# design.net
KiCad netlist of a schematic drawn in Altium Designer
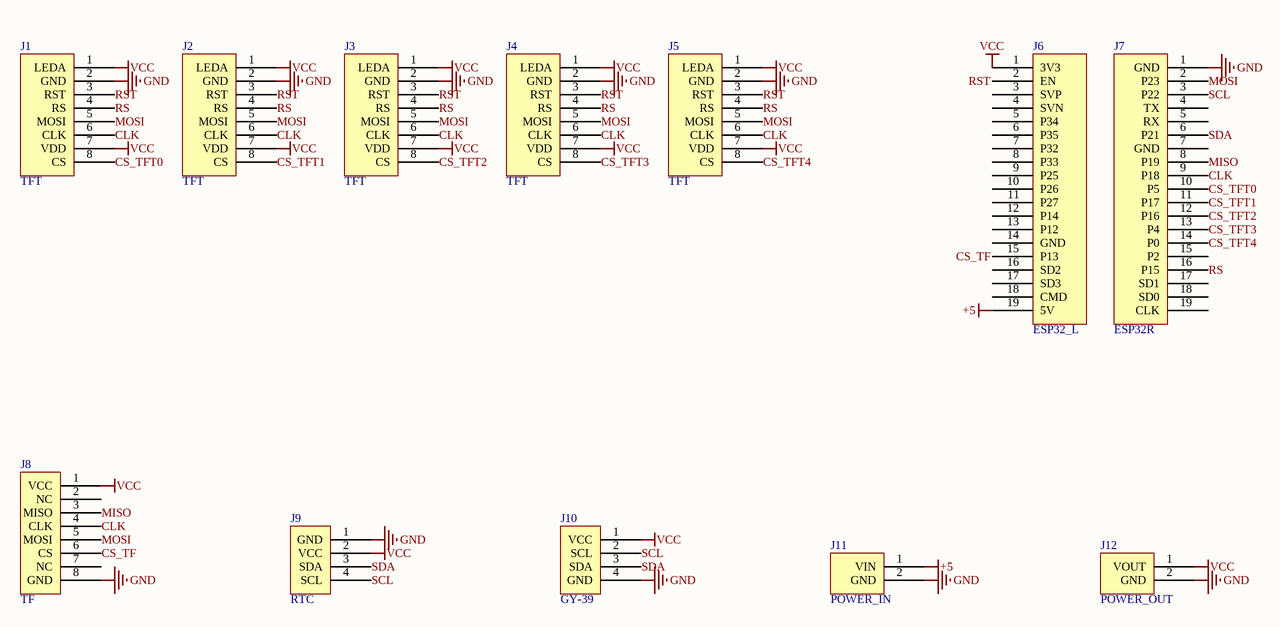
[diagram p0: 原理图.SchDoc]

(export (version "E")
  (design (tool "Eeschema 10.0.6"))
  (components
    (comp (ref "J1")
      (value "TFT")
      (footprint "MHDR1X8")
      (description "TFT槽")
      (libsource (lib "*") (part "1.14 tft"))
    )
    (comp (ref "J2")
      (value "TFT")
      (footprint "MHDR1X8")
      (description "TFT槽")
      (libsource (lib "*") (part "1.14 tft"))
    )
    (comp (ref "J3")
      (value "TFT")
      (footprint "MHDR1X8")
      (description "TFT槽")
      (libsource (lib "*") (part "1.14 tft"))
    )
    (comp (ref "J4")
      (value "TFT")
      (footprint "MHDR1X8")
      (description "TFT槽")
      (libsource (lib "*") (part "1.14 tft"))
    )
    (comp (ref "J5")
      (value "TFT")
      (footprint "MHDR1X8")
      (description "TFT槽")
      (libsource (lib "*") (part "1.14 tft"))
    )
    (comp (ref "J6")
      (value "ESP32_L")
      (footprint "MHDR1X19")
      (description "ESP32左槽")
      (libsource (lib "*") (part "ESP32-S_L"))
    )
    (comp (ref "J7")
      (value "ESP32R")
      (footprint "MHDR1X19")
      (description "ESP32右槽")
      (libsource (lib "*") (part "ESP32-S_R"))
    )
    (comp (ref "J8")
      (value "TF")
      (footprint "MHDR1X8")
      (description "TF卡模块槽")
      (libsource (lib "*") (part "TF card"))
    )
    (comp (ref "J9")
      (value "RTC")
      (footprint "MHDR1X4")
      (description "时钟模块槽")
      (libsource (lib "*") (part "RTC"))
    )
    (comp (ref "J10")
      (value "GY-39")
      (footprint "MHDR1X4")
      (description "GY-39模块槽")
      (libsource (lib "*") (part "GY-39"))
    )
    (comp (ref "J11") (value "POWER_IN") (footprint "MHDR1X2") (libsource (lib "*") (part "POWER_IN")))
    (comp (ref "J12") (value "POWER_OUT") (footprint "MHDR1X2") (libsource (lib "*") (part "POWER_OUT")))
  )
  (nets
    (net (code "1") (name "+5") (class "Default")
      (node (ref "J11") (pin "1") (pinfunction "VIN_1") (pintype "passive"))
      (node (ref "J6") (pin "19") (pinfunction "5V_19") (pintype "passive"))
    )
    (net (code "2") (name "/CLK") (class "Default")
      (node (ref "J1") (pin "6") (pinfunction "CLK_6") (pintype "passive"))
      (node (ref "J2") (pin "6") (pinfunction "CLK_6") (pintype "passive"))
      (node (ref "J3") (pin "6") (pinfunction "CLK_6") (pintype "passive"))
      (node (ref "J4") (pin "6") (pinfunction "CLK_6") (pintype "passive"))
      (node (ref "J5") (pin "6") (pinfunction "CLK_6") (pintype "passive"))
      (node (ref "J7") (pin "9") (pinfunction "P18_9") (pintype "passive"))
      (node (ref "J8") (pin "4") (pinfunction "CLK_4") (pintype "passive"))
    )
    (net (code "3") (name "/CS_TF") (class "Default")
      (node (ref "J6") (pin "15") (pinfunction "P13_15") (pintype "passive"))
      (node (ref "J8") (pin "6") (pinfunction "CS_6") (pintype "passive"))
    )
    (net (code "4") (name "/CS_TFT0") (class "Default")
      (node (ref "J1") (pin "8") (pinfunction "CS_8") (pintype "passive"))
      (node (ref "J7") (pin "10") (pinfunction "P5_10") (pintype "passive"))
    )
    (net (code "5") (name "/CS_TFT1") (class "Default")
      (node (ref "J2") (pin "8") (pinfunction "CS_8") (pintype "passive"))
      (node (ref "J7") (pin "11") (pinfunction "P17_11") (pintype "passive"))
    )
    (net (code "6") (name "/CS_TFT2") (class "Default")
      (node (ref "J3") (pin "8") (pinfunction "CS_8") (pintype "passive"))
      (node (ref "J7") (pin "12") (pinfunction "P16_12") (pintype "passive"))
    )
    (net (code "7") (name "/CS_TFT3") (class "Default")
      (node (ref "J4") (pin "8") (pinfunction "CS_8") (pintype "passive"))
      (node (ref "J7") (pin "13") (pinfunction "P4_13") (pintype "passive"))
    )
    (net (code "8") (name "/CS_TFT4") (class "Default")
      (node (ref "J5") (pin "8") (pinfunction "CS_8") (pintype "passive"))
      (node (ref "J7") (pin "14") (pinfunction "P0_14") (pintype "passive"))
    )
    (net (code "9") (name "/MISO") (class "Default")
      (node (ref "J7") (pin "8") (pinfunction "P19_8") (pintype "passive"))
      (node (ref "J8") (pin "3") (pinfunction "MISO_3") (pintype "passive"))
    )
    (net (code "10") (name "/MOSI") (class "Default")
      (node (ref "J1") (pin "5") (pinfunction "MOSI_5") (pintype "passive"))
      (node (ref "J2") (pin "5") (pinfunction "MOSI_5") (pintype "passive"))
      (node (ref "J3") (pin "5") (pinfunction "MOSI_5") (pintype "passive"))
      (node (ref "J4") (pin "5") (pinfunction "MOSI_5") (pintype "passive"))
      (node (ref "J5") (pin "5") (pinfunction "MOSI_5") (pintype "passive"))
      (node (ref "J7") (pin "2") (pinfunction "P23_2") (pintype "passive"))
      (node (ref "J8") (pin "5") (pinfunction "MOSI_5") (pintype "passive"))
    )
    (net (code "11") (name "/RS") (class "Default")
      (node (ref "J1") (pin "4") (pinfunction "RS_4") (pintype "passive"))
      (node (ref "J2") (pin "4") (pinfunction "RS_4") (pintype "passive"))
      (node (ref "J3") (pin "4") (pinfunction "RS_4") (pintype "passive"))
      (node (ref "J4") (pin "4") (pinfunction "RS_4") (pintype "passive"))
      (node (ref "J5") (pin "4") (pinfunction "RS_4") (pintype "passive"))
      (node (ref "J7") (pin "16") (pinfunction "P15_16") (pintype "passive"))
    )
    (net (code "12") (name "/RST") (class "Default")
      (node (ref "J1") (pin "3") (pinfunction "RST_3") (pintype "passive"))
      (node (ref "J2") (pin "3") (pinfunction "RST_3") (pintype "passive"))
      (node (ref "J3") (pin "3") (pinfunction "RST_3") (pintype "passive"))
      (node (ref "J4") (pin "3") (pinfunction "RST_3") (pintype "passive"))
      (node (ref "J5") (pin "3") (pinfunction "RST_3") (pintype "passive"))
      (node (ref "J6") (pin "2") (pinfunction "EN_2") (pintype "passive"))
    )
    (net (code "13") (name "/SCL") (class "Default")
      (node (ref "J10") (pin "2") (pinfunction "SCL_2") (pintype "passive"))
      (node (ref "J7") (pin "3") (pinfunction "P22_3") (pintype "passive"))
      (node (ref "J9") (pin "4") (pinfunction "SCL_4") (pintype "passive"))
    )
    (net (code "14") (name "/SDA") (class "Default")
      (node (ref "J10") (pin "3") (pinfunction "SDA_3") (pintype "passive"))
      (node (ref "J7") (pin "6") (pinfunction "P21_6") (pintype "passive"))
      (node (ref "J9") (pin "3") (pinfunction "SDA_3") (pintype "passive"))
    )
    (net (code "15") (name "GND") (class "Default")
      (node (ref "J1") (pin "2") (pinfunction "GND_2") (pintype "passive"))
      (node (ref "J10") (pin "4") (pinfunction "GND_4") (pintype "passive"))
      (node (ref "J11") (pin "2") (pinfunction "GND_2") (pintype "passive"))
      (node (ref "J12") (pin "2") (pinfunction "GND_2") (pintype "passive"))
      (node (ref "J2") (pin "2") (pinfunction "GND_2") (pintype "passive"))
      (node (ref "J3") (pin "2") (pinfunction "GND_2") (pintype "passive"))
      (node (ref "J4") (pin "2") (pinfunction "GND_2") (pintype "passive"))
      (node (ref "J5") (pin "2") (pinfunction "GND_2") (pintype "passive"))
      (node (ref "J7") (pin "1") (pinfunction "GND_1") (pintype "passive"))
      (node (ref "J8") (pin "8") (pinfunction "GND_8") (pintype "passive"))
      (node (ref "J9") (pin "1") (pinfunction "GND_1") (pintype "passive"))
    )
    (net (code "16") (name "VCC") (class "Default")
      (node (ref "J1") (pin "1") (pinfunction "LEDA_1") (pintype "passive"))
      (node (ref "J1") (pin "7") (pinfunction "VDD_7") (pintype "passive"))
      (node (ref "J10") (pin "1") (pinfunction "VCC_1") (pintype "passive"))
      (node (ref "J12") (pin "1") (pinfunction "VOUT_1") (pintype "passive"))
      (node (ref "J2") (pin "1") (pinfunction "LEDA_1") (pintype "passive"))
      (node (ref "J2") (pin "7") (pinfunction "VDD_7") (pintype "passive"))
      (node (ref "J3") (pin "1") (pinfunction "LEDA_1") (pintype "passive"))
      (node (ref "J3") (pin "7") (pinfunction "VDD_7") (pintype "passive"))
      (node (ref "J4") (pin "1") (pinfunction "LEDA_1") (pintype "passive"))
      (node (ref "J4") (pin "7") (pinfunction "VDD_7") (pintype "passive"))
      (node (ref "J5") (pin "1") (pinfunction "LEDA_1") (pintype "passive"))
      (node (ref "J5") (pin "7") (pinfunction "VDD_7") (pintype "passive"))
      (node (ref "J6") (pin "1") (pinfunction "3V3_1") (pintype "passive"))
      (node (ref "J8") (pin "1") (pinfunction "VCC_1") (pintype "passive"))
      (node (ref "J9") (pin "2") (pinfunction "VCC_2") (pintype "passive"))
    )
    (net (code "17") (name "unconnected-(J6-CMD-Pad18)") (class "Default")
      (node (ref "J6") (pin "18") (pinfunction "CMD_18") (pintype "passive"))
    )
    (net (code "18") (name "unconnected-(J6-GND-Pad14)") (class "Default")
      (node (ref "J6") (pin "14") (pinfunction "GND_14") (pintype "passive"))
    )
    (net (code "19") (name "unconnected-(J6-P12-Pad13)") (class "Default")
      (node (ref "J6") (pin "13") (pinfunction "P12_13") (pintype "passive"))
    )
    (net (code "20") (name "unconnected-(J6-P14-Pad12)") (class "Default")
      (node (ref "J6") (pin "12") (pinfunction "P14_12") (pintype "passive"))
    )
    (net (code "21") (name "unconnected-(J6-P25-Pad9)") (class "Default")
      (node (ref "J6") (pin "9") (pinfunction "P25_9") (pintype "passive"))
    )
    (net (code "22") (name "unconnected-(J6-P26-Pad10)") (class "Default")
      (node (ref "J6") (pin "10") (pinfunction "P26_10") (pintype "passive"))
    )
    (net (code "23") (name "unconnected-(J6-P27-Pad11)") (class "Default")
      (node (ref "J6") (pin "11") (pinfunction "P27_11") (pintype "passive"))
    )
    (net (code "24") (name "unconnected-(J6-P32-Pad7)") (class "Default")
      (node (ref "J6") (pin "7") (pinfunction "P32_7") (pintype "passive"))
    )
    (net (code "25") (name "unconnected-(J6-P33-Pad8)") (class "Default")
      (node (ref "J6") (pin "8") (pinfunction "P33_8") (pintype "passive"))
    )
    (net (code "26") (name "unconnected-(J6-P34-Pad5)") (class "Default")
      (node (ref "J6") (pin "5") (pinfunction "P34_5") (pintype "passive"))
    )
    (net (code "27") (name "unconnected-(J6-P35-Pad6)") (class "Default")
      (node (ref "J6") (pin "6") (pinfunction "P35_6") (pintype "passive"))
    )
    (net (code "28") (name "unconnected-(J6-SD2-Pad16)") (class "Default")
      (node (ref "J6") (pin "16") (pinfunction "SD2_16") (pintype "passive"))
    )
    (net (code "29") (name "unconnected-(J6-SD3-Pad17)") (class "Default")
      (node (ref "J6") (pin "17") (pinfunction "SD3_17") (pintype "passive"))
    )
    (net (code "30") (name "unconnected-(J6-SVN-Pad4)") (class "Default")
      (node (ref "J6") (pin "4") (pinfunction "SVN_4") (pintype "passive"))
    )
    (net (code "31") (name "unconnected-(J6-SVP-Pad3)") (class "Default")
      (node (ref "J6") (pin "3") (pinfunction "SVP_3") (pintype "passive"))
    )
    (net (code "32") (name "unconnected-(J7-CLK-Pad19)") (class "Default")
      (node (ref "J7") (pin "19") (pinfunction "CLK_19") (pintype "passive"))
    )
    (net (code "33") (name "unconnected-(J7-GND-Pad7)") (class "Default")
      (node (ref "J7") (pin "7") (pinfunction "GND_7") (pintype "passive"))
    )
    (net (code "34") (name "unconnected-(J7-P2-Pad15)") (class "Default")
      (node (ref "J7") (pin "15") (pinfunction "P2_15") (pintype "passive"))
    )
    (net (code "35") (name "unconnected-(J7-RX-Pad5)") (class "Default")
      (node (ref "J7") (pin "5") (pinfunction "RX_5") (pintype "passive"))
    )
    (net (code "36") (name "unconnected-(J7-SD0-Pad18)") (class "Default")
      (node (ref "J7") (pin "18") (pinfunction "SD0_18") (pintype "passive"))
    )
    (net (code "37") (name "unconnected-(J7-SD1-Pad17)") (class "Default")
      (node (ref "J7") (pin "17") (pinfunction "SD1_17") (pintype "passive"))
    )
    (net (code "38") (name "unconnected-(J7-TX-Pad4)") (class "Default")
      (node (ref "J7") (pin "4") (pinfunction "TX_4") (pintype "passive"))
    )
    (net (code "39") (name "unconnected-(J8-NC-Pad2)") (class "Default")
      (node (ref "J8") (pin "2") (pinfunction "NC_2") (pintype "passive"))
    )
    (net (code "40") (name "unconnected-(J8-NC-Pad7)") (class "Default")
      (node (ref "J8") (pin "7") (pinfunction "NC_7") (pintype "passive"))
    )
  )
)
